# topwithprogport.net
KiCad netlist of a schematic drawn in EAGLE
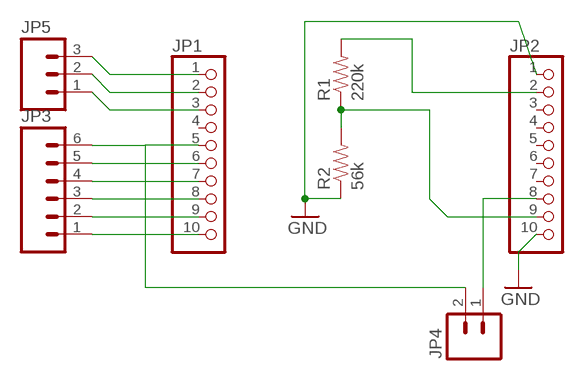
[diagram p0: schematic, sheet 1]

(export (version "E")
  (design (tool "Eeschema 10.0.6"))
  (components
    (comp (ref "JP1")
      (value "PINHD-1X10")
      (footprint "eagle-import:1X10")
      (libsource (lib "eagle-import") (part "PINHD-1X10"))
    )
    (comp (ref "JP2")
      (value "PINHD-1X10")
      (footprint "eagle-import:1X10")
      (libsource (lib "eagle-import") (part "PINHD-1X10"))
    )
    (comp (ref "JP3")
      (value "M06LONGPADS")
      (footprint "eagle-import:1X06_LONGPADS")
      (libsource (lib "eagle-import") (part "M06LONGPADS"))
    )
    (comp (ref "JP4")
      (value "M02LOCK_LONGPADS")
      (footprint "eagle-import:1X02_LOCK_LONGPADS")
      (libsource (lib "eagle-import") (part "M02LOCK_LONGPADS"))
    )
    (comp (ref "JP5")
      (value "M03LOCK_LONGPADS")
      (footprint "eagle-import:1X03_LOCK_LONGPADS")
      (libsource (lib "eagle-import") (part "M03LOCK_LONGPADS"))
    )
    (comp (ref "R1")
      (value "220k")
      (footprint "eagle-import:AXIAL-0.4")
      (libsource (lib "eagle-import") (part "RESISTORPTH-1/4W"))
    )
    (comp (ref "R2")
      (value "56k")
      (footprint "eagle-import:AXIAL-0.4")
      (libsource (lib "eagle-import") (part "RESISTORPTH-1/4W"))
    )
  )
  (nets
    (net (code "1") (name "GND") (class "Default")
      (node (ref "JP1") (pin "1") (pinfunction "1_1") (pintype "passive"))
      (node (ref "JP2") (pin "1") (pinfunction "1_1") (pintype "passive"))
      (node (ref "JP2") (pin "10") (pinfunction "10_10") (pintype "passive"))
      (node (ref "JP5") (pin "3") (pinfunction "3_3") (pintype "passive"))
      (node (ref "R2") (pin "P$1") (pinfunction "1_P$1") (pintype "passive"))
    )
    (net (code "2") (name "Net-(JP1-Pad2)") (class "Default")
      (node (ref "JP1") (pin "2") (pinfunction "2_2") (pintype "passive"))
      (node (ref "JP5") (pin "2") (pinfunction "2_2") (pintype "passive"))
    )
    (net (code "3") (name "Net-(JP1-Pad3)") (class "Default")
      (node (ref "JP1") (pin "3") (pinfunction "3_3") (pintype "passive"))
      (node (ref "JP5") (pin "1") (pinfunction "1_1") (pintype "passive"))
    )
    (net (code "4") (name "Net-(JP1-Pad5)") (class "Default")
      (node (ref "JP1") (pin "5") (pinfunction "5_5") (pintype "passive"))
      (node (ref "JP3") (pin "6") (pinfunction "6_6") (pintype "passive"))
      (node (ref "JP4") (pin "2") (pinfunction "2_2") (pintype "passive"))
    )
    (net (code "5") (name "Net-(JP1-Pad6)") (class "Default")
      (node (ref "JP1") (pin "6") (pinfunction "6_6") (pintype "passive"))
      (node (ref "JP3") (pin "5") (pinfunction "5_5") (pintype "passive"))
    )
    (net (code "6") (name "Net-(JP1-Pad7)") (class "Default")
      (node (ref "JP1") (pin "7") (pinfunction "7_7") (pintype "passive"))
      (node (ref "JP3") (pin "4") (pinfunction "4_4") (pintype "passive"))
    )
    (net (code "7") (name "Net-(JP1-Pad8)") (class "Default")
      (node (ref "JP1") (pin "8") (pinfunction "8_8") (pintype "passive"))
      (node (ref "JP3") (pin "3") (pinfunction "3_3") (pintype "passive"))
    )
    (net (code "8") (name "Net-(JP1-Pad9)") (class "Default")
      (node (ref "JP1") (pin "9") (pinfunction "9_9") (pintype "passive"))
      (node (ref "JP3") (pin "2") (pinfunction "2_2") (pintype "passive"))
    )
    (net (code "9") (name "Net-(JP1-Pad10)") (class "Default")
      (node (ref "JP1") (pin "10") (pinfunction "10_10") (pintype "passive"))
      (node (ref "JP3") (pin "1") (pinfunction "1_1") (pintype "passive"))
    )
    (net (code "10") (name "Net-(JP2-Pad8)") (class "Default")
      (node (ref "JP2") (pin "8") (pinfunction "8_8") (pintype "passive"))
      (node (ref "JP4") (pin "1") (pinfunction "1_1") (pintype "passive"))
    )
    (net (code "11") (name "Net-(R1-1)") (class "Default")
      (node (ref "JP2") (pin "9") (pinfunction "9_9") (pintype "passive"))
      (node (ref "R1") (pin "P$1") (pinfunction "1_P$1") (pintype "passive"))
      (node (ref "R2") (pin "P$2") (pinfunction "2_P$2") (pintype "passive"))
    )
    (net (code "12") (name "Net-(R1-2)") (class "Default")
      (node (ref "JP2") (pin "2") (pinfunction "2_2") (pintype "passive"))
      (node (ref "R1") (pin "P$2") (pinfunction "2_P$2") (pintype "passive"))
    )
    (net (code "13") (name "unconnected-(JP1-Pad4)") (class "Default")
      (node (ref "JP1") (pin "4") (pinfunction "4_4") (pintype "passive"))
    )
    (net (code "14") (name "unconnected-(JP2-Pad3)") (class "Default")
      (node (ref "JP2") (pin "3") (pinfunction "3_3") (pintype "passive"))
    )
    (net (code "15") (name "unconnected-(JP2-Pad4)") (class "Default")
      (node (ref "JP2") (pin "4") (pinfunction "4_4") (pintype "passive"))
    )
    (net (code "16") (name "unconnected-(JP2-Pad5)") (class "Default")
      (node (ref "JP2") (pin "5") (pinfunction "5_5") (pintype "passive"))
    )
    (net (code "17") (name "unconnected-(JP2-Pad6)") (class "Default")
      (node (ref "JP2") (pin "6") (pinfunction "6_6") (pintype "passive"))
    )
    (net (code "18") (name "unconnected-(JP2-Pad7)") (class "Default")
      (node (ref "JP2") (pin "7") (pinfunction "7_7") (pintype "passive"))
    )
  )
)
